# atmega_embedded_main_2.net
KiCad netlist of a schematic drawn in EAGLE
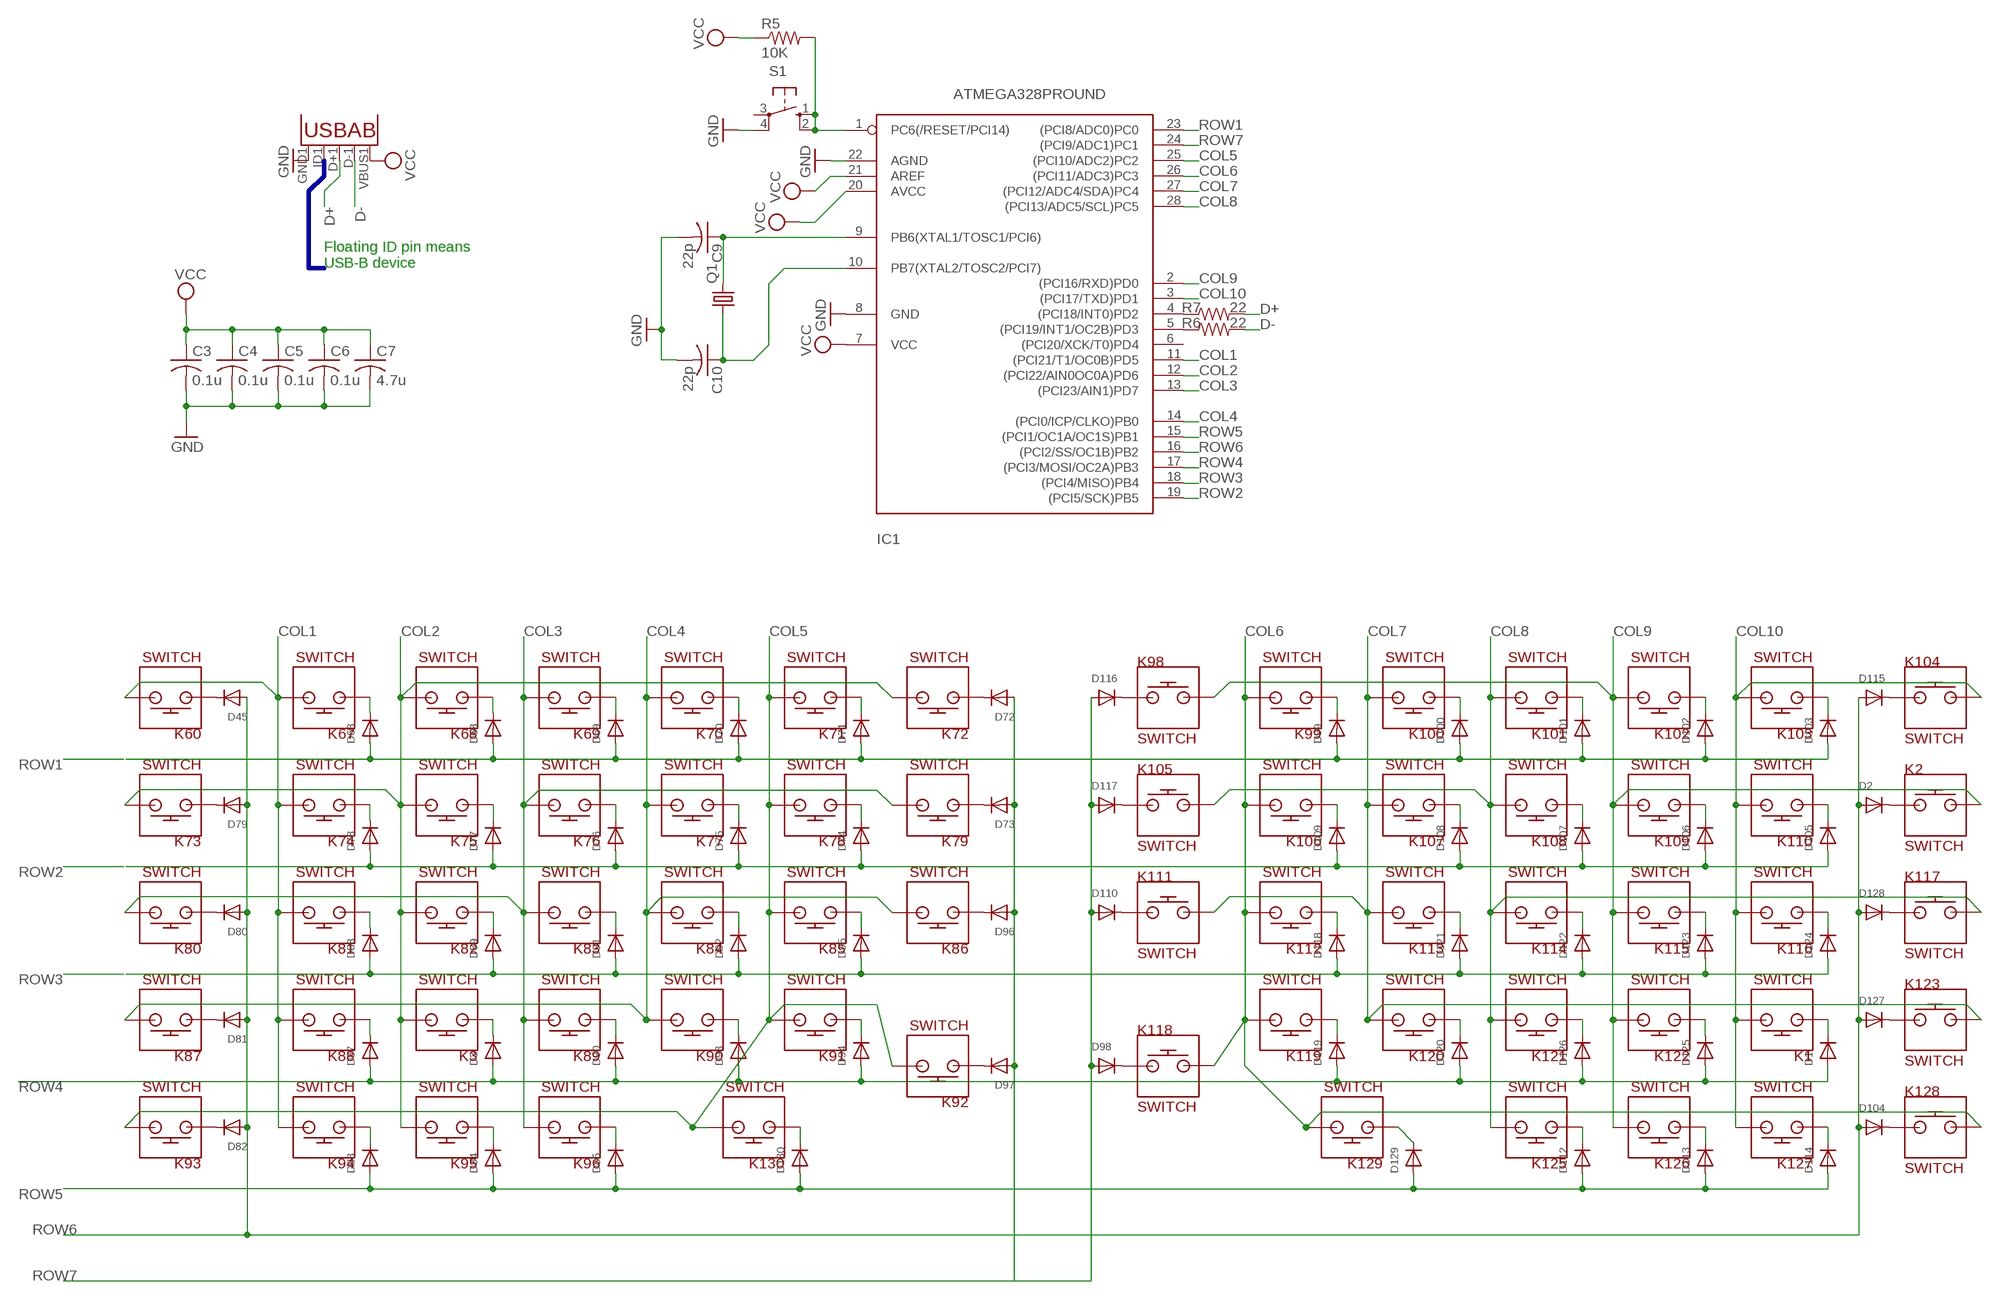
[diagram p0: schematic, sheet 1]

(export (version "E")
  (design (tool "Eeschema 10.0.6"))
  (components
    (comp (ref "C3")
      (value "0.1u")
      (footprint "eagle-import:C0805")
      (libsource (lib "eagle-import") (part "C-USC0805"))
    )
    (comp (ref "C4")
      (value "0.1u")
      (footprint "eagle-import:C0805")
      (libsource (lib "eagle-import") (part "C-USC0805"))
    )
    (comp (ref "C5")
      (value "0.1u")
      (footprint "eagle-import:C0805")
      (libsource (lib "eagle-import") (part "C-USC0805"))
    )
    (comp (ref "C6")
      (value "0.1u")
      (footprint "eagle-import:C0805")
      (libsource (lib "eagle-import") (part "C-USC0805"))
    )
    (comp (ref "C7")
      (value "4.7u")
      (footprint "eagle-import:C0805")
      (libsource (lib "eagle-import") (part "C-USC0805"))
    )
    (comp (ref "C9")
      (value "22p")
      (footprint "eagle-import:C0805")
      (libsource (lib "eagle-import") (part "C-USC0805"))
    )
    (comp (ref "C10")
      (value "22p")
      (footprint "eagle-import:C0805")
      (libsource (lib "eagle-import") (part "C-USC0805"))
    )
    (comp (ref "D1")
      (value "DIODESMA")
      (footprint "eagle-import:SMADIODE")
      (libsource (lib "eagle-import") (part "DIODESMA"))
    )
    (comp (ref "D2")
      (value "DIODESMA")
      (footprint "eagle-import:SMADIODE")
      (libsource (lib "eagle-import") (part "DIODESMA"))
    )
    (comp (ref "D3")
      (value "DIODESMA")
      (footprint "eagle-import:SMADIODE")
      (libsource (lib "eagle-import") (part "DIODESMA"))
    )
    (comp (ref "D45")
      (value "DIODESMA")
      (footprint "eagle-import:SMADIODE")
      (libsource (lib "eagle-import") (part "DIODESMA"))
    )
    (comp (ref "D63")
      (value "DIODESMA")
      (footprint "eagle-import:SMADIODE")
      (libsource (lib "eagle-import") (part "DIODESMA"))
    )
    (comp (ref "D68")
      (value "DIODESMA")
      (footprint "eagle-import:SMADIODE")
      (libsource (lib "eagle-import") (part "DIODESMA"))
    )
    (comp (ref "D69")
      (value "DIODESMA")
      (footprint "eagle-import:SMADIODE")
      (libsource (lib "eagle-import") (part "DIODESMA"))
    )
    (comp (ref "D70")
      (value "DIODESMA")
      (footprint "eagle-import:SMADIODE")
      (libsource (lib "eagle-import") (part "DIODESMA"))
    )
    (comp (ref "D71")
      (value "DIODESMA")
      (footprint "eagle-import:SMADIODE")
      (libsource (lib "eagle-import") (part "DIODESMA"))
    )
    (comp (ref "D72")
      (value "DIODESMA")
      (footprint "eagle-import:SMADIODE")
      (libsource (lib "eagle-import") (part "DIODESMA"))
    )
    (comp (ref "D73")
      (value "DIODESMA")
      (footprint "eagle-import:SMADIODE")
      (libsource (lib "eagle-import") (part "DIODESMA"))
    )
    (comp (ref "D74")
      (value "DIODESMA")
      (footprint "eagle-import:SMADIODE")
      (libsource (lib "eagle-import") (part "DIODESMA"))
    )
    (comp (ref "D75")
      (value "DIODESMA")
      (footprint "eagle-import:SMADIODE")
      (libsource (lib "eagle-import") (part "DIODESMA"))
    )
    (comp (ref "D76")
      (value "DIODESMA")
      (footprint "eagle-import:SMADIODE")
      (libsource (lib "eagle-import") (part "DIODESMA"))
    )
    (comp (ref "D77")
      (value "DIODESMA")
      (footprint "eagle-import:SMADIODE")
      (libsource (lib "eagle-import") (part "DIODESMA"))
    )
    (comp (ref "D78")
      (value "DIODESMA")
      (footprint "eagle-import:SMADIODE")
      (libsource (lib "eagle-import") (part "DIODESMA"))
    )
    (comp (ref "D79")
      (value "DIODESMA")
      (footprint "eagle-import:SMADIODE")
      (libsource (lib "eagle-import") (part "DIODESMA"))
    )
    (comp (ref "D80")
      (value "DIODESMA")
      (footprint "eagle-import:SMADIODE")
      (libsource (lib "eagle-import") (part "DIODESMA"))
    )
    (comp (ref "D81")
      (value "DIODESMA")
      (footprint "eagle-import:SMADIODE")
      (libsource (lib "eagle-import") (part "DIODESMA"))
    )
    (comp (ref "D82")
      (value "DIODESMA")
      (footprint "eagle-import:SMADIODE")
      (libsource (lib "eagle-import") (part "DIODESMA"))
    )
    (comp (ref "D83")
      (value "DIODESMA")
      (footprint "eagle-import:SMADIODE")
      (libsource (lib "eagle-import") (part "DIODESMA"))
    )
    (comp (ref "D84")
      (value "DIODESMA")
      (footprint "eagle-import:SMADIODE")
      (libsource (lib "eagle-import") (part "DIODESMA"))
    )
    (comp (ref "D85")
      (value "DIODESMA")
      (footprint "eagle-import:SMADIODE")
      (libsource (lib "eagle-import") (part "DIODESMA"))
    )
    (comp (ref "D87")
      (value "DIODESMA")
      (footprint "eagle-import:SMADIODE")
      (libsource (lib "eagle-import") (part "DIODESMA"))
    )
    (comp (ref "D88")
      (value "DIODESMA")
      (footprint "eagle-import:SMADIODE")
      (libsource (lib "eagle-import") (part "DIODESMA"))
    )
    (comp (ref "D89")
      (value "DIODESMA")
      (footprint "eagle-import:SMADIODE")
      (libsource (lib "eagle-import") (part "DIODESMA"))
    )
    (comp (ref "D90")
      (value "DIODESMA")
      (footprint "eagle-import:SMADIODE")
      (libsource (lib "eagle-import") (part "DIODESMA"))
    )
    (comp (ref "D91")
      (value "DIODESMA")
      (footprint "eagle-import:SMADIODE")
      (libsource (lib "eagle-import") (part "DIODESMA"))
    )
    (comp (ref "D92")
      (value "DIODESMA")
      (footprint "eagle-import:SMADIODE")
      (libsource (lib "eagle-import") (part "DIODESMA"))
    )
    (comp (ref "D93")
      (value "DIODESMA")
      (footprint "eagle-import:SMADIODE")
      (libsource (lib "eagle-import") (part "DIODESMA"))
    )
    (comp (ref "D94")
      (value "DIODESMA")
      (footprint "eagle-import:SMADIODE")
      (libsource (lib "eagle-import") (part "DIODESMA"))
    )
    (comp (ref "D95")
      (value "DIODESMA")
      (footprint "eagle-import:SMADIODE")
      (libsource (lib "eagle-import") (part "DIODESMA"))
    )
    (comp (ref "D96")
      (value "DIODESMA")
      (footprint "eagle-import:SMADIODE")
      (libsource (lib "eagle-import") (part "DIODESMA"))
    )
    (comp (ref "D97")
      (value "DIODESMA")
      (footprint "eagle-import:SMADIODE")
      (libsource (lib "eagle-import") (part "DIODESMA"))
    )
    (comp (ref "D98")
      (value "DIODESMA")
      (footprint "eagle-import:SMADIODE")
      (libsource (lib "eagle-import") (part "DIODESMA"))
    )
    (comp (ref "D99")
      (value "DIODESMA")
      (footprint "eagle-import:SMADIODE")
      (libsource (lib "eagle-import") (part "DIODESMA"))
    )
    (comp (ref "D100")
      (value "DIODESMA")
      (footprint "eagle-import:SMADIODE")
      (libsource (lib "eagle-import") (part "DIODESMA"))
    )
    (comp (ref "D101")
      (value "DIODESMA")
      (footprint "eagle-import:SMADIODE")
      (libsource (lib "eagle-import") (part "DIODESMA"))
    )
    (comp (ref "D102")
      (value "DIODESMA")
      (footprint "eagle-import:SMADIODE")
      (libsource (lib "eagle-import") (part "DIODESMA"))
    )
    (comp (ref "D103")
      (value "DIODESMA")
      (footprint "eagle-import:SMADIODE")
      (libsource (lib "eagle-import") (part "DIODESMA"))
    )
    (comp (ref "D104")
      (value "DIODESMA")
      (footprint "eagle-import:SMADIODE")
      (libsource (lib "eagle-import") (part "DIODESMA"))
    )
    (comp (ref "D105")
      (value "DIODESMA")
      (footprint "eagle-import:SMADIODE")
      (libsource (lib "eagle-import") (part "DIODESMA"))
    )
    (comp (ref "D106")
      (value "DIODESMA")
      (footprint "eagle-import:SMADIODE")
      (libsource (lib "eagle-import") (part "DIODESMA"))
    )
    (comp (ref "D107")
      (value "DIODESMA")
      (footprint "eagle-import:SMADIODE")
      (libsource (lib "eagle-import") (part "DIODESMA"))
    )
    (comp (ref "D108")
      (value "DIODESMA")
      (footprint "eagle-import:SMADIODE")
      (libsource (lib "eagle-import") (part "DIODESMA"))
    )
    (comp (ref "D109")
      (value "DIODESMA")
      (footprint "eagle-import:SMADIODE")
      (libsource (lib "eagle-import") (part "DIODESMA"))
    )
    (comp (ref "D110")
      (value "DIODESMA")
      (footprint "eagle-import:SMADIODE")
      (libsource (lib "eagle-import") (part "DIODESMA"))
    )
    (comp (ref "D112")
      (value "DIODESMA")
      (footprint "eagle-import:SMADIODE")
      (libsource (lib "eagle-import") (part "DIODESMA"))
    )
    (comp (ref "D113")
      (value "DIODESMA")
      (footprint "eagle-import:SMADIODE")
      (libsource (lib "eagle-import") (part "DIODESMA"))
    )
    (comp (ref "D114")
      (value "DIODESMA")
      (footprint "eagle-import:SMADIODE")
      (libsource (lib "eagle-import") (part "DIODESMA"))
    )
    (comp (ref "D115")
      (value "DIODESMA")
      (footprint "eagle-import:SMADIODE")
      (libsource (lib "eagle-import") (part "DIODESMA"))
    )
    (comp (ref "D116")
      (value "DIODESMA")
      (footprint "eagle-import:SMADIODE")
      (libsource (lib "eagle-import") (part "DIODESMA"))
    )
    (comp (ref "D117")
      (value "DIODESMA")
      (footprint "eagle-import:SMADIODE")
      (libsource (lib "eagle-import") (part "DIODESMA"))
    )
    (comp (ref "D118")
      (value "DIODESMA")
      (footprint "eagle-import:SMADIODE")
      (libsource (lib "eagle-import") (part "DIODESMA"))
    )
    (comp (ref "D119")
      (value "DIODESMA")
      (footprint "eagle-import:SMADIODE")
      (libsource (lib "eagle-import") (part "DIODESMA"))
    )
    (comp (ref "D120")
      (value "DIODESMA")
      (footprint "eagle-import:SMADIODE")
      (libsource (lib "eagle-import") (part "DIODESMA"))
    )
    (comp (ref "D121")
      (value "DIODESMA")
      (footprint "eagle-import:SMADIODE")
      (libsource (lib "eagle-import") (part "DIODESMA"))
    )
    (comp (ref "D122")
      (value "DIODESMA")
      (footprint "eagle-import:SMADIODE")
      (libsource (lib "eagle-import") (part "DIODESMA"))
    )
    (comp (ref "D123")
      (value "DIODESMA")
      (footprint "eagle-import:SMADIODE")
      (libsource (lib "eagle-import") (part "DIODESMA"))
    )
    (comp (ref "D124")
      (value "DIODESMA")
      (footprint "eagle-import:SMADIODE")
      (libsource (lib "eagle-import") (part "DIODESMA"))
    )
    (comp (ref "D125")
      (value "DIODESMA")
      (footprint "eagle-import:SMADIODE")
      (libsource (lib "eagle-import") (part "DIODESMA"))
    )
    (comp (ref "D126")
      (value "DIODESMA")
      (footprint "eagle-import:SMADIODE")
      (libsource (lib "eagle-import") (part "DIODESMA"))
    )
    (comp (ref "D127")
      (value "DIODESMA")
      (footprint "eagle-import:SMADIODE")
      (libsource (lib "eagle-import") (part "DIODESMA"))
    )
    (comp (ref "D128")
      (value "DIODESMA")
      (footprint "eagle-import:SMADIODE")
      (libsource (lib "eagle-import") (part "DIODESMA"))
    )
    (comp (ref "D129")
      (value "DIODESMA")
      (footprint "eagle-import:SMADIODE")
      (libsource (lib "eagle-import") (part "DIODESMA"))
    )
    (comp (ref "D130")
      (value "DIODESMA")
      (footprint "eagle-import:SMADIODE")
      (libsource (lib "eagle-import") (part "DIODESMA"))
    )
    (comp (ref "IC1")
      (value "ATMEGA328PROUND")
      (footprint "eagle-import:DIL28-3-ROUND")
      (libsource (lib "eagle-import") (part "ATMEGA328PROUND"))
    )
    (comp (ref "K1")
      (value "SWITCH")
      (footprint "eagle-import:KAILH_LOW_PROFILE")
      (libsource (lib "eagle-import") (part "SWITCH"))
    )
    (comp (ref "K2")
      (value "SWITCH")
      (footprint "eagle-import:KAILH_LOW_PROFILE")
      (libsource (lib "eagle-import") (part "SWITCH"))
    )
    (comp (ref "K3")
      (value "SWITCH")
      (footprint "eagle-import:KAILH_LOW_PROFILE")
      (libsource (lib "eagle-import") (part "SWITCH"))
    )
    (comp (ref "K60")
      (value "SWITCH")
      (footprint "eagle-import:KAILH_LOW_PROFILE")
      (libsource (lib "eagle-import") (part "SWITCH"))
    )
    (comp (ref "K67")
      (value "SWITCH")
      (footprint "eagle-import:KAILH_LOW_PROFILE")
      (libsource (lib "eagle-import") (part "SWITCH"))
    )
    (comp (ref "K68")
      (value "SWITCH")
      (footprint "eagle-import:KAILH_LOW_PROFILE")
      (libsource (lib "eagle-import") (part "SWITCH"))
    )
    (comp (ref "K69")
      (value "SWITCH")
      (footprint "eagle-import:KAILH_LOW_PROFILE")
      (libsource (lib "eagle-import") (part "SWITCH"))
    )
    (comp (ref "K70")
      (value "SWITCH")
      (footprint "eagle-import:KAILH_LOW_PROFILE")
      (libsource (lib "eagle-import") (part "SWITCH"))
    )
    (comp (ref "K71")
      (value "SWITCH")
      (footprint "eagle-import:KAILH_LOW_PROFILE")
      (libsource (lib "eagle-import") (part "SWITCH"))
    )
    (comp (ref "K72")
      (value "SWITCH")
      (footprint "eagle-import:KAILH_LOW_PROFILE")
      (libsource (lib "eagle-import") (part "SWITCH"))
    )
    (comp (ref "K73")
      (value "SWITCH")
      (footprint "eagle-import:KAILH_LOW_PROFILE")
      (libsource (lib "eagle-import") (part "SWITCH"))
    )
    (comp (ref "K74")
      (value "SWITCH")
      (footprint "eagle-import:KAILH_LOW_PROFILE")
      (libsource (lib "eagle-import") (part "SWITCH"))
    )
    (comp (ref "K75")
      (value "SWITCH")
      (footprint "eagle-import:KAILH_LOW_PROFILE")
      (libsource (lib "eagle-import") (part "SWITCH"))
    )
    (comp (ref "K76")
      (value "SWITCH")
      (footprint "eagle-import:KAILH_LOW_PROFILE")
      (libsource (lib "eagle-import") (part "SWITCH"))
    )
    (comp (ref "K77")
      (value "SWITCH")
      (footprint "eagle-import:KAILH_LOW_PROFILE")
      (libsource (lib "eagle-import") (part "SWITCH"))
    )
    (comp (ref "K78")
      (value "SWITCH")
      (footprint "eagle-import:KAILH_LOW_PROFILE")
      (libsource (lib "eagle-import") (part "SWITCH"))
    )
    (comp (ref "K79")
      (value "SWITCH")
      (footprint "eagle-import:KAILH_LOW_PROFILE")
      (libsource (lib "eagle-import") (part "SWITCH"))
    )
    (comp (ref "K80")
      (value "SWITCH")
      (footprint "eagle-import:KAILH_LOW_PROFILE")
      (libsource (lib "eagle-import") (part "SWITCH"))
    )
    (comp (ref "K81")
      (value "SWITCH")
      (footprint "eagle-import:KAILH_LOW_PROFILE")
      (libsource (lib "eagle-import") (part "SWITCH"))
    )
    (comp (ref "K82")
      (value "SWITCH")
      (footprint "eagle-import:KAILH_LOW_PROFILE")
      (libsource (lib "eagle-import") (part "SWITCH"))
    )
    (comp (ref "K83")
      (value "SWITCH")
      (footprint "eagle-import:KAILH_LOW_PROFILE")
      (libsource (lib "eagle-import") (part "SWITCH"))
    )
    (comp (ref "K84")
      (value "SWITCH")
      (footprint "eagle-import:KAILH_LOW_PROFILE")
      (libsource (lib "eagle-import") (part "SWITCH"))
    )
    (comp (ref "K85")
      (value "SWITCH")
      (footprint "eagle-import:KAILH_LOW_PROFILE")
      (libsource (lib "eagle-import") (part "SWITCH"))
    )
    (comp (ref "K86")
      (value "SWITCH")
      (footprint "eagle-import:KAILH_LOW_PROFILE")
      (libsource (lib "eagle-import") (part "SWITCH"))
    )
    (comp (ref "K87")
      (value "SWITCH")
      (footprint "eagle-import:KAILH_LOW_PROFILE")
      (libsource (lib "eagle-import") (part "SWITCH"))
    )
    (comp (ref "K88")
      (value "SWITCH")
      (footprint "eagle-import:KAILH_LOW_PROFILE")
      (libsource (lib "eagle-import") (part "SWITCH"))
    )
    (comp (ref "K89")
      (value "SWITCH")
      (footprint "eagle-import:KAILH_LOW_PROFILE")
      (libsource (lib "eagle-import") (part "SWITCH"))
    )
    (comp (ref "K90")
      (value "SWITCH")
      (footprint "eagle-import:KAILH_LOW_PROFILE")
      (libsource (lib "eagle-import") (part "SWITCH"))
    )
    (comp (ref "K91")
      (value "SWITCH")
      (footprint "eagle-import:KAILH_LOW_PROFILE")
      (libsource (lib "eagle-import") (part "SWITCH"))
    )
    (comp (ref "K92")
      (value "SWITCH")
      (footprint "eagle-import:KAILH_LOW_PROFILE")
      (libsource (lib "eagle-import") (part "SWITCH"))
    )
    (comp (ref "K93")
      (value "SWITCH")
      (footprint "eagle-import:KAILH_LOW_PROFILE")
      (libsource (lib "eagle-import") (part "SWITCH"))
    )
    (comp (ref "K94")
      (value "SWITCH")
      (footprint "eagle-import:KAILH_LOW_PROFILE")
      (libsource (lib "eagle-import") (part "SWITCH"))
    )
    (comp (ref "K95")
      (value "SWITCH")
      (footprint "eagle-import:KAILH_LOW_PROFILE")
      (libsource (lib "eagle-import") (part "SWITCH"))
    )
    (comp (ref "K96")
      (value "SWITCH")
      (footprint "eagle-import:KAILH_LOW_PROFILE")
      (libsource (lib "eagle-import") (part "SWITCH"))
    )
    (comp (ref "K98")
      (value "SWITCH")
      (footprint "eagle-import:KAILH_LOW_PROFILE")
      (libsource (lib "eagle-import") (part "SWITCH"))
    )
    (comp (ref "K99")
      (value "SWITCH")
      (footprint "eagle-import:KAILH_LOW_PROFILE")
      (libsource (lib "eagle-import") (part "SWITCH"))
    )
    (comp (ref "K100")
      (value "SWITCH")
      (footprint "eagle-import:KAILH_LOW_PROFILE")
      (libsource (lib "eagle-import") (part "SWITCH"))
    )
    (comp (ref "K101")
      (value "SWITCH")
      (footprint "eagle-import:KAILH_LOW_PROFILE")
      (libsource (lib "eagle-import") (part "SWITCH"))
    )
    (comp (ref "K102")
      (value "SWITCH")
      (footprint "eagle-import:KAILH_LOW_PROFILE")
      (libsource (lib "eagle-import") (part "SWITCH"))
    )
    (comp (ref "K103")
      (value "SWITCH")
      (footprint "eagle-import:KAILH_LOW_PROFILE")
      (libsource (lib "eagle-import") (part "SWITCH"))
    )
    (comp (ref "K104")
      (value "SWITCH")
      (footprint "eagle-import:KAILH_LOW_PROFILE")
      (libsource (lib "eagle-import") (part "SWITCH"))
    )
    (comp (ref "K105")
      (value "SWITCH")
      (footprint "eagle-import:KAILH_LOW_PROFILE")
      (libsource (lib "eagle-import") (part "SWITCH"))
    )
    (comp (ref "K106")
      (value "SWITCH")
      (footprint "eagle-import:KAILH_LOW_PROFILE")
      (libsource (lib "eagle-import") (part "SWITCH"))
    )
    (comp (ref "K107")
      (value "SWITCH")
      (footprint "eagle-import:KAILH_LOW_PROFILE")
      (libsource (lib "eagle-import") (part "SWITCH"))
    )
    (comp (ref "K108")
      (value "SWITCH")
      (footprint "eagle-import:KAILH_LOW_PROFILE")
      (libsource (lib "eagle-import") (part "SWITCH"))
    )
    (comp (ref "K109")
      (value "SWITCH")
      (footprint "eagle-import:KAILH_LOW_PROFILE")
      (libsource (lib "eagle-import") (part "SWITCH"))
    )
    (comp (ref "K110")
      (value "SWITCH")
      (footprint "eagle-import:KAILH_LOW_PROFILE")
      (libsource (lib "eagle-import") (part "SWITCH"))
    )
    (comp (ref "K111")
      (value "SWITCH")
      (footprint "eagle-import:KAILH_LOW_PROFILE")
      (libsource (lib "eagle-import") (part "SWITCH"))
    )
    (comp (ref "K112")
      (value "SWITCH")
      (footprint "eagle-import:KAILH_LOW_PROFILE")
      (libsource (lib "eagle-import") (part "SWITCH"))
    )
    (comp (ref "K113")
      (value "SWITCH")
      (footprint "eagle-import:KAILH_LOW_PROFILE")
      (libsource (lib "eagle-import") (part "SWITCH"))
    )
    (comp (ref "K114")
      (value "SWITCH")
      (footprint "eagle-import:KAILH_LOW_PROFILE")
      (libsource (lib "eagle-import") (part "SWITCH"))
    )
    (comp (ref "K115")
      (value "SWITCH")
      (footprint "eagle-import:KAILH_LOW_PROFILE")
      (libsource (lib "eagle-import") (part "SWITCH"))
    )
    (comp (ref "K116")
      (value "SWITCH")
      (footprint "eagle-import:KAILH_LOW_PROFILE")
      (libsource (lib "eagle-import") (part "SWITCH"))
    )
    (comp (ref "K117")
      (value "SWITCH")
      (footprint "eagle-import:KAILH_LOW_PROFILE")
      (libsource (lib "eagle-import") (part "SWITCH"))
    )
    (comp (ref "K118")
      (value "SWITCH")
      (footprint "eagle-import:KAILH_LOW_PROFILE")
      (libsource (lib "eagle-import") (part "SWITCH"))
    )
    (comp (ref "K119")
      (value "SWITCH")
      (footprint "eagle-import:KAILH_LOW_PROFILE")
      (libsource (lib "eagle-import") (part "SWITCH"))
    )
    (comp (ref "K120")
      (value "SWITCH")
      (footprint "eagle-import:KAILH_LOW_PROFILE")
      (libsource (lib "eagle-import") (part "SWITCH"))
    )
    (comp (ref "K121")
      (value "SWITCH")
      (footprint "eagle-import:KAILH_LOW_PROFILE")
      (libsource (lib "eagle-import") (part "SWITCH"))
    )
    (comp (ref "K122")
      (value "SWITCH")
      (footprint "eagle-import:KAILH_LOW_PROFILE")
      (libsource (lib "eagle-import") (part "SWITCH"))
    )
    (comp (ref "K123")
      (value "SWITCH")
      (footprint "eagle-import:KAILH_LOW_PROFILE")
      (libsource (lib "eagle-import") (part "SWITCH"))
    )
    (comp (ref "K125")
      (value "SWITCH")
      (footprint "eagle-import:KAILH_LOW_PROFILE")
      (libsource (lib "eagle-import") (part "SWITCH"))
    )
    (comp (ref "K126")
      (value "SWITCH")
      (footprint "eagle-import:KAILH_LOW_PROFILE")
      (libsource (lib "eagle-import") (part "SWITCH"))
    )
    (comp (ref "K127")
      (value "SWITCH")
      (footprint "eagle-import:KAILH_LOW_PROFILE")
      (libsource (lib "eagle-import") (part "SWITCH"))
    )
    (comp (ref "K128")
      (value "SWITCH")
      (footprint "eagle-import:KAILH_LOW_PROFILE")
      (libsource (lib "eagle-import") (part "SWITCH"))
    )
    (comp (ref "K129")
      (value "SWITCH")
      (footprint "eagle-import:KAILH_LOW_PROFILE")
      (libsource (lib "eagle-import") (part "SWITCH"))
    )
    (comp (ref "K130")
      (value "SWITCH")
      (footprint "eagle-import:KAILH_LOW_PROFILE")
      (libsource (lib "eagle-import") (part "SWITCH"))
    )
    (comp (ref "Q1")
      (value "CRYSTALHC49S")
      (footprint "eagle-import:HC49_S")
      (libsource (lib "eagle-import") (part "CRYSTALHC49S"))
    )
    (comp (ref "R5")
      (value "10K")
      (footprint "eagle-import:M0805")
      (libsource (lib "eagle-import") (part "R-US_M0805"))
    )
    (comp (ref "R6")
      (value "22")
      (footprint "eagle-import:M0805")
      (libsource (lib "eagle-import") (part "R-US_M0805"))
    )
    (comp (ref "R7")
      (value "22")
      (footprint "eagle-import:M0805")
      (libsource (lib "eagle-import") (part "R-US_M0805"))
    )
    (comp (ref "S1")
      (value "10-XX")
      (footprint "eagle-import:B3F-10XX")
      (fields (field (name "MPN") "B3F-1000"))
      (libsource (lib "eagle-import") (part "10-XX"))
    )
    (comp (ref "U1")
      (value "USB\"\"")
      (footprint "eagle-import:USB-MICRO-SMD")
      (libsource (lib "eagle-import") (part "USB{dblquote}{dblquote}"))
    )
  )
  (nets
    (net (code "1") (name "/COL1") (class "Default")
      (node (ref "IC1") (pin "11") (pinfunction "(PCI21/T1/OC0B)PD5_11") (pintype "bidirectional"))
      (node (ref "K60") (pin "P$2") (pinfunction "P$2_P$2") (pintype "bidirectional"))
      (node (ref "K67") (pin "P$2") (pinfunction "P$2_P$2") (pintype "bidirectional"))
      (node (ref "K74") (pin "P$2") (pinfunction "P$2_P$2") (pintype "bidirectional"))
      (node (ref "K81") (pin "P$2") (pinfunction "P$2_P$2") (pintype "bidirectional"))
      (node (ref "K88") (pin "P$2") (pinfunction "P$2_P$2") (pintype "bidirectional"))
      (node (ref "K94") (pin "P$2") (pinfunction "P$2_P$2") (pintype "bidirectional"))
    )
    (net (code "2") (name "/COL2") (class "Default")
      (node (ref "IC1") (pin "12") (pinfunction "(PCI22/AIN0OC0A)PD6_12") (pintype "bidirectional"))
      (node (ref "K3") (pin "P$2") (pinfunction "P$2_P$2") (pintype "bidirectional"))
      (node (ref "K68") (pin "P$2") (pinfunction "P$2_P$2") (pintype "bidirectional"))
      (node (ref "K72") (pin "P$2") (pinfunction "P$2_P$2") (pintype "bidirectional"))
      (node (ref "K73") (pin "P$2") (pinfunction "P$2_P$2") (pintype "bidirectional"))
      (node (ref "K75") (pin "P$2") (pinfunction "P$2_P$2") (pintype "bidirectional"))
      (node (ref "K82") (pin "P$2") (pinfunction "P$2_P$2") (pintype "bidirectional"))
      (node (ref "K95") (pin "P$2") (pinfunction "P$2_P$2") (pintype "bidirectional"))
    )
    (net (code "3") (name "/COL3") (class "Default")
      (node (ref "IC1") (pin "13") (pinfunction "(PCI23/AIN1)PD7_13") (pintype "bidirectional"))
      (node (ref "K69") (pin "P$2") (pinfunction "P$2_P$2") (pintype "bidirectional"))
      (node (ref "K76") (pin "P$2") (pinfunction "P$2_P$2") (pintype "bidirectional"))
      (node (ref "K79") (pin "P$2") (pinfunction "P$2_P$2") (pintype "bidirectional"))
      (node (ref "K80") (pin "P$2") (pinfunction "P$2_P$2") (pintype "bidirectional"))
      (node (ref "K83") (pin "P$2") (pinfunction "P$2_P$2") (pintype "bidirectional"))
      (node (ref "K89") (pin "P$2") (pinfunction "P$2_P$2") (pintype "bidirectional"))
      (node (ref "K96") (pin "P$2") (pinfunction "P$2_P$2") (pintype "bidirectional"))
    )
    (net (code "4") (name "/COL4") (class "Default")
      (node (ref "IC1") (pin "14") (pinfunction "(PCI0/ICP/CLKO)PB0_14") (pintype "bidirectional"))
      (node (ref "K70") (pin "P$2") (pinfunction "P$2_P$2") (pintype "bidirectional"))
      (node (ref "K77") (pin "P$2") (pinfunction "P$2_P$2") (pintype "bidirectional"))
      (node (ref "K84") (pin "P$2") (pinfunction "P$2_P$2") (pintype "bidirectional"))
      (node (ref "K86") (pin "P$2") (pinfunction "P$2_P$2") (pintype "bidirectional"))
      (node (ref "K87") (pin "P$2") (pinfunction "P$2_P$2") (pintype "bidirectional"))
      (node (ref "K90") (pin "P$2") (pinfunction "P$2_P$2") (pintype "bidirectional"))
    )
    (net (code "5") (name "/COL5") (class "Default")
      (node (ref "IC1") (pin "25") (pinfunction "(PCI10/ADC2)PC2_25") (pintype "bidirectional"))
      (node (ref "K130") (pin "P$2") (pinfunction "P$2_P$2") (pintype "bidirectional"))
      (node (ref "K71") (pin "P$2") (pinfunction "P$2_P$2") (pintype "bidirectional"))
      (node (ref "K78") (pin "P$2") (pinfunction "P$2_P$2") (pintype "bidirectional"))
      (node (ref "K85") (pin "P$2") (pinfunction "P$2_P$2") (pintype "bidirectional"))
      (node (ref "K91") (pin "P$2") (pinfunction "P$2_P$2") (pintype "bidirectional"))
      (node (ref "K92") (pin "P$2") (pinfunction "P$2_P$2") (pintype "bidirectional"))
      (node (ref "K93") (pin "P$2") (pinfunction "P$2_P$2") (pintype "bidirectional"))
    )
    (net (code "6") (name "/COL6") (class "Default")
      (node (ref "IC1") (pin "26") (pinfunction "(PCI11/ADC3)PC3_26") (pintype "bidirectional"))
      (node (ref "K106") (pin "P$2") (pinfunction "P$2_P$2") (pintype "bidirectional"))
      (node (ref "K112") (pin "P$2") (pinfunction "P$2_P$2") (pintype "bidirectional"))
      (node (ref "K118") (pin "P$2") (pinfunction "P$2_P$2") (pintype "bidirectional"))
      (node (ref "K119") (pin "P$2") (pinfunction "P$2_P$2") (pintype "bidirectional"))
      (node (ref "K128") (pin "P$2") (pinfunction "P$2_P$2") (pintype "bidirectional"))
      (node (ref "K129") (pin "P$2") (pinfunction "P$2_P$2") (pintype "bidirectional"))
      (node (ref "K99") (pin "P$2") (pinfunction "P$2_P$2") (pintype "bidirectional"))
    )
    (net (code "7") (name "/COL7") (class "Default")
      (node (ref "IC1") (pin "27") (pinfunction "(PCI12/ADC4/SDA)PC4_27") (pintype "bidirectional"))
      (node (ref "K100") (pin "P$2") (pinfunction "P$2_P$2") (pintype "bidirectional"))
      (node (ref "K107") (pin "P$2") (pinfunction "P$2_P$2") (pintype "bidirectional"))
      (node (ref "K111") (pin "P$2") (pinfunction "P$2_P$2") (pintype "bidirectional"))
      (node (ref "K113") (pin "P$2") (pinfunction "P$2_P$2") (pintype "bidirectional"))
      (node (ref "K120") (pin "P$2") (pinfunction "P$2_P$2") (pintype "bidirectional"))
      (node (ref "K123") (pin "P$2") (pinfunction "P$2_P$2") (pintype "bidirectional"))
    )
    (net (code "8") (name "/COL8") (class "Default")
      (node (ref "IC1") (pin "28") (pinfunction "(PCI13/ADC5/SCL)PC5_28") (pintype "bidirectional"))
      (node (ref "K101") (pin "P$2") (pinfunction "P$2_P$2") (pintype "bidirectional"))
      (node (ref "K105") (pin "P$2") (pinfunction "P$2_P$2") (pintype "bidirectional"))
      (node (ref "K108") (pin "P$2") (pinfunction "P$2_P$2") (pintype "bidirectional"))
      (node (ref "K114") (pin "P$2") (pinfunction "P$2_P$2") (pintype "bidirectional"))
      (node (ref "K117") (pin "P$2") (pinfunction "P$2_P$2") (pintype "bidirectional"))
      (node (ref "K121") (pin "P$2") (pinfunction "P$2_P$2") (pintype "bidirectional"))
      (node (ref "K125") (pin "P$2") (pinfunction "P$2_P$2") (pintype "bidirectional"))
    )
    (net (code "9") (name "/COL9") (class "Default")
      (node (ref "IC1") (pin "2") (pinfunction "(PCI16/RXD)PD0_2") (pintype "bidirectional"))
      (node (ref "K102") (pin "P$2") (pinfunction "P$2_P$2") (pintype "bidirectional"))
      (node (ref "K109") (pin "P$2") (pinfunction "P$2_P$2") (pintype "bidirectional"))
      (node (ref "K115") (pin "P$2") (pinfunction "P$2_P$2") (pintype "bidirectional"))
      (node (ref "K122") (pin "P$2") (pinfunction "P$2_P$2") (pintype "bidirectional"))
      (node (ref "K126") (pin "P$2") (pinfunction "P$2_P$2") (pintype "bidirectional"))
      (node (ref "K2") (pin "P$2") (pinfunction "P$2_P$2") (pintype "bidirectional"))
      (node (ref "K98") (pin "P$2") (pinfunction "P$2_P$2") (pintype "bidirectional"))
    )
    (net (code "10") (name "/COL10") (class "Default")
      (node (ref "IC1") (pin "3") (pinfunction "(PCI17/TXD)PD1_3") (pintype "bidirectional"))
      (node (ref "K1") (pin "P$2") (pinfunction "P$2_P$2") (pintype "bidirectional"))
      (node (ref "K103") (pin "P$2") (pinfunction "P$2_P$2") (pintype "bidirectional"))
      (node (ref "K104") (pin "P$2") (pinfunction "P$2_P$2") (pintype "bidirectional"))
      (node (ref "K110") (pin "P$2") (pinfunction "P$2_P$2") (pintype "bidirectional"))
      (node (ref "K116") (pin "P$2") (pinfunction "P$2_P$2") (pintype "bidirectional"))
      (node (ref "K127") (pin "P$2") (pinfunction "P$2_P$2") (pintype "bidirectional"))
    )
    (net (code "11") (name "/D+") (class "Default")
      (node (ref "R7") (pin "2") (pinfunction "2_2") (pintype "passive"))
      (node (ref "U1") (pin "D+1") (pinfunction "D+_D+1") (pintype "bidirectional"))
    )
    (net (code "12") (name "/D-") (class "Default")
      (node (ref "R6") (pin "2") (pinfunction "2_2") (pintype "passive"))
      (node (ref "U1") (pin "D-1") (pinfunction "D-_D-1") (pintype "bidirectional"))
    )
    (net (code "13") (name "/ROW1") (class "Default")
      (node (ref "D100") (pin "A") (pinfunction "A_A") (pintype "passive"))
      (node (ref "D101") (pin "A") (pinfunction "A_A") (pintype "passive"))
      (node (ref "D102") (pin "A") (pinfunction "A_A") (pintype "passive"))
      (node (ref "D103") (pin "A") (pinfunction "A_A") (pintype "passive"))
      (node (ref "D63") (pin "A") (pinfunction "A_A") (pintype "passive"))
      (node (ref "D68") (pin "A") (pinfunction "A_A") (pintype "passive"))
      (node (ref "D69") (pin "A") (pinfunction "A_A") (pintype "passive"))
      (node (ref "D70") (pin "A") (pinfunction "A_A") (pintype "passive"))
      (node (ref "D71") (pin "A") (pinfunction "A_A") (pintype "passive"))
      (node (ref "D99") (pin "A") (pinfunction "A_A") (pintype "passive"))
      (node (ref "IC1") (pin "23") (pinfunction "(PCI8/ADC0)PC0_23") (pintype "bidirectional"))
    )
    (net (code "14") (name "/ROW2") (class "Default")
      (node (ref "D105") (pin "A") (pinfunction "A_A") (pintype "passive"))
      (node (ref "D106") (pin "A") (pinfunction "A_A") (pintype "passive"))
      (node (ref "D107") (pin "A") (pinfunction "A_A") (pintype "passive"))
      (node (ref "D108") (pin "A") (pinfunction "A_A") (pintype "passive"))
      (node (ref "D109") (pin "A") (pinfunction "A_A") (pintype "passive"))
      (node (ref "D74") (pin "A") (pinfunction "A_A") (pintype "passive"))
      (node (ref "D75") (pin "A") (pinfunction "A_A") (pintype "passive"))
      (node (ref "D76") (pin "A") (pinfunction "A_A") (pintype "passive"))
      (node (ref "D77") (pin "A") (pinfunction "A_A") (pintype "passive"))
      (node (ref "D78") (pin "A") (pinfunction "A_A") (pintype "passive"))
      (node (ref "IC1") (pin "19") (pinfunction "(PCI5/SCK)PB5_19") (pintype "bidirectional"))
    )
    (net (code "15") (name "/ROW3") (class "Default")
      (node (ref "D118") (pin "A") (pinfunction "A_A") (pintype "passive"))
      (node (ref "D121") (pin "A") (pinfunction "A_A") (pintype "passive"))
      (node (ref "D122") (pin "A") (pinfunction "A_A") (pintype "passive"))
      (node (ref "D123") (pin "A") (pinfunction "A_A") (pintype "passive"))
      (node (ref "D124") (pin "A") (pinfunction "A_A") (pintype "passive"))
      (node (ref "D88") (pin "A") (pinfunction "A_A") (pintype "passive"))
      (node (ref "D89") (pin "A") (pinfunction "A_A") (pintype "passive"))
      (node (ref "D91") (pin "A") (pinfunction "A_A") (pintype "passive"))
      (node (ref "D92") (pin "A") (pinfunction "A_A") (pintype "passive"))
      (node (ref "D95") (pin "A") (pinfunction "A_A") (pintype "passive"))
      (node (ref "IC1") (pin "18") (pinfunction "(PCI4/MISO)PB4_18") (pintype "bidirectional"))
    )
    (net (code "16") (name "/ROW4") (class "Default")
      (node (ref "D1") (pin "A") (pinfunction "A_A") (pintype "passive"))
      (node (ref "D119") (pin "A") (pinfunction "A_A") (pintype "passive"))
      (node (ref "D120") (pin "A") (pinfunction "A_A") (pintype "passive"))
      (node (ref "D125") (pin "A") (pinfunction "A_A") (pintype "passive"))
      (node (ref "D126") (pin "A") (pinfunction "A_A") (pintype "passive"))
      (node (ref "D3") (pin "A") (pinfunction "A_A") (pintype "passive"))
      (node (ref "D87") (pin "A") (pinfunction "A_A") (pintype "passive"))
      (node (ref "D90") (pin "A") (pinfunction "A_A") (pintype "passive"))
      (node (ref "D93") (pin "A") (pinfunction "A_A") (pintype "passive"))
      (node (ref "D94") (pin "A") (pinfunction "A_A") (pintype "passive"))
      (node (ref "IC1") (pin "17") (pinfunction "(PCI3/MOSI/OC2A)PB3_17") (pintype "bidirectional"))
    )
    (net (code "17") (name "/ROW5") (class "Default")
      (node (ref "D112") (pin "A") (pinfunction "A_A") (pintype "passive"))
      (node (ref "D113") (pin "A") (pinfunction "A_A") (pintype "passive"))
      (node (ref "D114") (pin "A") (pinfunction "A_A") (pintype "passive"))
      (node (ref "D129") (pin "A") (pinfunction "A_A") (pintype "passive"))
      (node (ref "D130") (pin "A") (pinfunction "A_A") (pintype "passive"))
      (node (ref "D83") (pin "A") (pinfunction "A_A") (pintype "passive"))
      (node (ref "D84") (pin "A") (pinfunction "A_A") (pintype "passive"))
      (node (ref "D85") (pin "A") (pinfunction "A_A") (pintype "passive"))
      (node (ref "IC1") (pin "15") (pinfunction "(PCI1/OC1A/OC1S)PB1_15") (pintype "bidirectional"))
    )
    (net (code "18") (name "/ROW6") (class "Default")
      (node (ref "D104") (pin "A") (pinfunction "A_A") (pintype "passive"))
      (node (ref "D115") (pin "A") (pinfunction "A_A") (pintype "passive"))
      (node (ref "D127") (pin "A") (pinfunction "A_A") (pintype "passive"))
      (node (ref "D128") (pin "A") (pinfunction "A_A") (pintype "passive"))
      (node (ref "D2") (pin "A") (pinfunction "A_A") (pintype "passive"))
      (node (ref "D45") (pin "A") (pinfunction "A_A") (pintype "passive"))
      (node (ref "D79") (pin "A") (pinfunction "A_A") (pintype "passive"))
      (node (ref "D80") (pin "A") (pinfunction "A_A") (pintype "passive"))
      (node (ref "D81") (pin "A") (pinfunction "A_A") (pintype "passive"))
      (node (ref "D82") (pin "A") (pinfunction "A_A") (pintype "passive"))
      (node (ref "IC1") (pin "16") (pinfunction "(PCI2/SS/OC1B)PB2_16") (pintype "bidirectional"))
    )
    (net (code "19") (name "/ROW7") (class "Default")
      (node (ref "D110") (pin "A") (pinfunction "A_A") (pintype "passive"))
      (node (ref "D116") (pin "A") (pinfunction "A_A") (pintype "passive"))
      (node (ref "D117") (pin "A") (pinfunction "A_A") (pintype "passive"))
      (node (ref "D72") (pin "A") (pinfunction "A_A") (pintype "passive"))
      (node (ref "D73") (pin "A") (pinfunction "A_A") (pintype "passive"))
      (node (ref "D96") (pin "A") (pinfunction "A_A") (pintype "passive"))
      (node (ref "D97") (pin "A") (pinfunction "A_A") (pintype "passive"))
      (node (ref "D98") (pin "A") (pinfunction "A_A") (pintype "passive"))
      (node (ref "IC1") (pin "24") (pinfunction "(PCI9/ADC1)PC1_24") (pintype "bidirectional"))
    )
    (net (code "20") (name "GND") (class "Default")
      (node (ref "C10") (pin "2") (pinfunction "2_2") (pintype "passive"))
      (node (ref "C3") (pin "2") (pinfunction "2_2") (pintype "passive"))
      (node (ref "C4") (pin "2") (pinfunction "2_2") (pintype "passive"))
      (node (ref "C5") (pin "2") (pinfunction "2_2") (pintype "passive"))
      (node (ref "C6") (pin "2") (pinfunction "2_2") (pintype "passive"))
      (node (ref "C7") (pin "2") (pinfunction "2_2") (pintype "passive"))
      (node (ref "C9") (pin "2") (pinfunction "2_2") (pintype "passive"))
      (node (ref "IC1") (pin "22") (pinfunction "AGND_22") (pintype "bidirectional"))
      (node (ref "IC1") (pin "8") (pinfunction "GND_8") (pintype "bidirectional"))
      (node (ref "S1") (pin "4") (pinfunction "P1_4") (pintype "passive"))
      (node (ref "U1") (pin "GND1") (pinfunction "GND_GND1") (pintype "bidirectional"))
    )
    (net (code "21") (name "Net-(D1-PadC)") (class "Default")
      (node (ref "D1") (pin "C") (pinfunction "C_C") (pintype "passive"))
      (node (ref "K1") (pin "P$1") (pinfunction "P$1_P$1") (pintype "bidirectional"))
    )
    (net (code "22") (name "Net-(D2-PadC)") (class "Default")
      (node (ref "D2") (pin "C") (pinfunction "C_C") (pintype "passive"))
      (node (ref "K2") (pin "P$1") (pinfunction "P$1_P$1") (pintype "bidirectional"))
    )
    (net (code "23") (name "Net-(D3-PadC)") (class "Default")
      (node (ref "D3") (pin "C") (pinfunction "C_C") (pintype "passive"))
      (node (ref "K3") (pin "P$1") (pinfunction "P$1_P$1") (pintype "bidirectional"))
    )
    (net (code "24") (name "Net-(D45-PadC)") (class "Default")
      (node (ref "D45") (pin "C") (pinfunction "C_C") (pintype "passive"))
      (node (ref "K60") (pin "P$1") (pinfunction "P$1_P$1") (pintype "bidirectional"))
    )
    (net (code "25") (name "Net-(D63-PadC)") (class "Default")
      (node (ref "D63") (pin "C") (pinfunction "C_C") (pintype "passive"))
      (node (ref "K67") (pin "P$1") (pinfunction "P$1_P$1") (pintype "bidirectional"))
    )
    (net (code "26") (name "Net-(D68-PadC)") (class "Default")
      (node (ref "D68") (pin "C") (pinfunction "C_C") (pintype "passive"))
      (node (ref "K68") (pin "P$1") (pinfunction "P$1_P$1") (pintype "bidirectional"))
    )
    (net (code "27") (name "Net-(D69-PadC)") (class "Default")
      (node (ref "D69") (pin "C") (pinfunction "C_C") (pintype "passive"))
      (node (ref "K69") (pin "P$1") (pinfunction "P$1_P$1") (pintype "bidirectional"))
    )
    (net (code "28") (name "Net-(D70-PadC)") (class "Default")
      (node (ref "D70") (pin "C") (pinfunction "C_C") (pintype "passive"))
      (node (ref "K70") (pin "P$1") (pinfunction "P$1_P$1") (pintype "bidirectional"))
    )
    (net (code "29") (name "Net-(D71-PadC)") (class "Default")
      (node (ref "D71") (pin "C") (pinfunction "C_C") (pintype "passive"))
      (node (ref "K71") (pin "P$1") (pinfunction "P$1_P$1") (pintype "bidirectional"))
    )
    (net (code "30") (name "Net-(D72-PadC)") (class "Default")
      (node (ref "D72") (pin "C") (pinfunction "C_C") (pintype "passive"))
      (node (ref "K72") (pin "P$1") (pinfunction "P$1_P$1") (pintype "bidirectional"))
    )
    (net (code "31") (name "Net-(D73-PadC)") (class "Default")
      (node (ref "D73") (pin "C") (pinfunction "C_C") (pintype "passive"))
      (node (ref "K79") (pin "P$1") (pinfunction "P$1_P$1") (pintype "bidirectional"))
    )
    (net (code "32") (name "Net-(D74-PadC)") (class "Default")
      (node (ref "D74") (pin "C") (pinfunction "C_C") (pintype "passive"))
      (node (ref "K78") (pin "P$1") (pinfunction "P$1_P$1") (pintype "bidirectional"))
    )
    (net (code "33") (name "Net-(D75-PadC)") (class "Default")
      (node (ref "D75") (pin "C") (pinfunction "C_C") (pintype "passive"))
      (node (ref "K77") (pin "P$1") (pinfunction "P$1_P$1") (pintype "bidirectional"))
    )
    (net (code "34") (name "Net-(D76-PadC)") (class "Default")
      (node (ref "D76") (pin "C") (pinfunction "C_C") (pintype "passive"))
      (node (ref "K76") (pin "P$1") (pinfunction "P$1_P$1") (pintype "bidirectional"))
    )
    (net (code "35") (name "Net-(D77-PadC)") (class "Default")
      (node (ref "D77") (pin "C") (pinfunction "C_C") (pintype "passive"))
      (node (ref "K75") (pin "P$1") (pinfunction "P$1_P$1") (pintype "bidirectional"))
    )
    (net (code "36") (name "Net-(D78-PadC)") (class "Default")
      (node (ref "D78") (pin "C") (pinfunction "C_C") (pintype "passive"))
      (node (ref "K74") (pin "P$1") (pinfunction "P$1_P$1") (pintype "bidirectional"))
    )
    (net (code "37") (name "Net-(D79-PadC)") (class "Default")
      (node (ref "D79") (pin "C") (pinfunction "C_C") (pintype "passive"))
      (node (ref "K73") (pin "P$1") (pinfunction "P$1_P$1") (pintype "bidirectional"))
    )
    (net (code "38") (name "Net-(D80-PadC)") (class "Default")
      (node (ref "D80") (pin "C") (pinfunction "C_C") (pintype "passive"))
      (node (ref "K80") (pin "P$1") (pinfunction "P$1_P$1") (pintype "bidirectional"))
    )
    (net (code "39") (name "Net-(D81-PadC)") (class "Default")
      (node (ref "D81") (pin "C") (pinfunction "C_C") (pintype "passive"))
      (node (ref "K87") (pin "P$1") (pinfunction "P$1_P$1") (pintype "bidirectional"))
    )
    (net (code "40") (name "Net-(D82-PadC)") (class "Default")
      (node (ref "D82") (pin "C") (pinfunction "C_C") (pintype "passive"))
      (node (ref "K93") (pin "P$1") (pinfunction "P$1_P$1") (pintype "bidirectional"))
    )
    (net (code "41") (name "Net-(D83-PadC)") (class "Default")
      (node (ref "D83") (pin "C") (pinfunction "C_C") (pintype "passive"))
      (node (ref "K94") (pin "P$1") (pinfunction "P$1_P$1") (pintype "bidirectional"))
    )
    (net (code "42") (name "Net-(D84-PadC)") (class "Default")
      (node (ref "D84") (pin "C") (pinfunction "C_C") (pintype "passive"))
      (node (ref "K95") (pin "P$1") (pinfunction "P$1_P$1") (pintype "bidirectional"))
    )
    (net (code "43") (name "Net-(D85-PadC)") (class "Default")
      (node (ref "D85") (pin "C") (pinfunction "C_C") (pintype "passive"))
      (node (ref "K96") (pin "P$1") (pinfunction "P$1_P$1") (pintype "bidirectional"))
    )
    (net (code "44") (name "Net-(D87-PadC)") (class "Default")
      (node (ref "D87") (pin "C") (pinfunction "C_C") (pintype "passive"))
      (node (ref "K88") (pin "P$1") (pinfunction "P$1_P$1") (pintype "bidirectional"))
    )
    (net (code "45") (name "Net-(D88-PadC)") (class "Default")
      (node (ref "D88") (pin "C") (pinfunction "C_C") (pintype "passive"))
      (node (ref "K81") (pin "P$1") (pinfunction "P$1_P$1") (pintype "bidirectional"))
    )
    (net (code "46") (name "Net-(D89-PadC)") (class "Default")
      (node (ref "D89") (pin "C") (pinfunction "C_C") (pintype "passive"))
      (node (ref "K82") (pin "P$1") (pinfunction "P$1_P$1") (pintype "bidirectional"))
    )
    (net (code "47") (name "Net-(D90-PadC)") (class "Default")
      (node (ref "D90") (pin "C") (pinfunction "C_C") (pintype "passive"))
      (node (ref "K89") (pin "P$1") (pinfunction "P$1_P$1") (pintype "bidirectional"))
    )
    (net (code "48") (name "Net-(D91-PadC)") (class "Default")
      (node (ref "D91") (pin "C") (pinfunction "C_C") (pintype "passive"))
      (node (ref "K83") (pin "P$1") (pinfunction "P$1_P$1") (pintype "bidirectional"))
    )
    (net (code "49") (name "Net-(D92-PadC)") (class "Default")
      (node (ref "D92") (pin "C") (pinfunction "C_C") (pintype "passive"))
      (node (ref "K84") (pin "P$1") (pinfunction "P$1_P$1") (pintype "bidirectional"))
    )
    (net (code "50") (name "Net-(D93-PadC)") (class "Default")
      (node (ref "D93") (pin "C") (pinfunction "C_C") (pintype "passive"))
      (node (ref "K90") (pin "P$1") (pinfunction "P$1_P$1") (pintype "bidirectional"))
    )
    (net (code "51") (name "Net-(D94-PadC)") (class "Default")
      (node (ref "D94") (pin "C") (pinfunction "C_C") (pintype "passive"))
      (node (ref "K91") (pin "P$1") (pinfunction "P$1_P$1") (pintype "bidirectional"))
    )
    (net (code "52") (name "Net-(D95-PadC)") (class "Default")
      (node (ref "D95") (pin "C") (pinfunction "C_C") (pintype "passive"))
      (node (ref "K85") (pin "P$1") (pinfunction "P$1_P$1") (pintype "bidirectional"))
    )
    (net (code "53") (name "Net-(D96-PadC)") (class "Default")
      (node (ref "D96") (pin "C") (pinfunction "C_C") (pintype "passive"))
      (node (ref "K86") (pin "P$1") (pinfunction "P$1_P$1") (pintype "bidirectional"))
    )
    (net (code "54") (name "Net-(D97-PadC)") (class "Default")
      (node (ref "D97") (pin "C") (pinfunction "C_C") (pintype "passive"))
      (node (ref "K92") (pin "P$1") (pinfunction "P$1_P$1") (pintype "bidirectional"))
    )
    (net (code "55") (name "Net-(D98-PadC)") (class "Default")
      (node (ref "D98") (pin "C") (pinfunction "C_C") (pintype "passive"))
      (node (ref "K118") (pin "P$1") (pinfunction "P$1_P$1") (pintype "bidirectional"))
    )
    (net (code "56") (name "Net-(D99-PadC)") (class "Default")
      (node (ref "D99") (pin "C") (pinfunction "C_C") (pintype "passive"))
      (node (ref "K99") (pin "P$1") (pinfunction "P$1_P$1") (pintype "bidirectional"))
    )
    (net (code "57") (name "Net-(D100-PadC)") (class "Default")
      (node (ref "D100") (pin "C") (pinfunction "C_C") (pintype "passive"))
      (node (ref "K100") (pin "P$1") (pinfunction "P$1_P$1") (pintype "bidirectional"))
    )
    (net (code "58") (name "Net-(D101-PadC)") (class "Default")
      (node (ref "D101") (pin "C") (pinfunction "C_C") (pintype "passive"))
      (node (ref "K101") (pin "P$1") (pinfunction "P$1_P$1") (pintype "bidirectional"))
    )
    (net (code "59") (name "Net-(D102-PadC)") (class "Default")
      (node (ref "D102") (pin "C") (pinfunction "C_C") (pintype "passive"))
      (node (ref "K102") (pin "P$1") (pinfunction "P$1_P$1") (pintype "bidirectional"))
    )
    (net (code "60") (name "Net-(D103-PadC)") (class "Default")
      (node (ref "D103") (pin "C") (pinfunction "C_C") (pintype "passive"))
      (node (ref "K103") (pin "P$1") (pinfunction "P$1_P$1") (pintype "bidirectional"))
    )
    (net (code "61") (name "Net-(D104-PadC)") (class "Default")
      (node (ref "D104") (pin "C") (pinfunction "C_C") (pintype "passive"))
      (node (ref "K128") (pin "P$1") (pinfunction "P$1_P$1") (pintype "bidirectional"))
    )
    (net (code "62") (name "Net-(D105-PadC)") (class "Default")
      (node (ref "D105") (pin "C") (pinfunction "C_C") (pintype "passive"))
      (node (ref "K110") (pin "P$1") (pinfunction "P$1_P$1") (pintype "bidirectional"))
    )
    (net (code "63") (name "Net-(D106-PadC)") (class "Default")
      (node (ref "D106") (pin "C") (pinfunction "C_C") (pintype "passive"))
      (node (ref "K109") (pin "P$1") (pinfunction "P$1_P$1") (pintype "bidirectional"))
    )
    (net (code "64") (name "Net-(D107-PadC)") (class "Default")
      (node (ref "D107") (pin "C") (pinfunction "C_C") (pintype "passive"))
      (node (ref "K108") (pin "P$1") (pinfunction "P$1_P$1") (pintype "bidirectional"))
    )
    (net (code "65") (name "Net-(D108-PadC)") (class "Default")
      (node (ref "D108") (pin "C") (pinfunction "C_C") (pintype "passive"))
      (node (ref "K107") (pin "P$1") (pinfunction "P$1_P$1") (pintype "bidirectional"))
    )
    (net (code "66") (name "Net-(D109-PadC)") (class "Default")
      (node (ref "D109") (pin "C") (pinfunction "C_C") (pintype "passive"))
      (node (ref "K106") (pin "P$1") (pinfunction "P$1_P$1") (pintype "bidirectional"))
    )
    (net (code "67") (name "Net-(D110-PadC)") (class "Default")
      (node (ref "D110") (pin "C") (pinfunction "C_C") (pintype "passive"))
      (node (ref "K111") (pin "P$1") (pinfunction "P$1_P$1") (pintype "bidirectional"))
    )
    (net (code "68") (name "Net-(D112-PadC)") (class "Default")
      (node (ref "D112") (pin "C") (pinfunction "C_C") (pintype "passive"))
      (node (ref "K125") (pin "P$1") (pinfunction "P$1_P$1") (pintype "bidirectional"))
    )
    (net (code "69") (name "Net-(D113-PadC)") (class "Default")
      (node (ref "D113") (pin "C") (pinfunction "C_C") (pintype "passive"))
      (node (ref "K126") (pin "P$1") (pinfunction "P$1_P$1") (pintype "bidirectional"))
    )
    (net (code "70") (name "Net-(D114-PadC)") (class "Default")
      (node (ref "D114") (pin "C") (pinfunction "C_C") (pintype "passive"))
      (node (ref "K127") (pin "P$1") (pinfunction "P$1_P$1") (pintype "bidirectional"))
    )
    (net (code "71") (name "Net-(D115-PadC)") (class "Default")
      (node (ref "D115") (pin "C") (pinfunction "C_C") (pintype "passive"))
      (node (ref "K104") (pin "P$1") (pinfunction "P$1_P$1") (pintype "bidirectional"))
    )
    (net (code "72") (name "Net-(D116-PadC)") (class "Default")
      (node (ref "D116") (pin "C") (pinfunction "C_C") (pintype "passive"))
      (node (ref "K98") (pin "P$1") (pinfunction "P$1_P$1") (pintype "bidirectional"))
    )
    (net (code "73") (name "Net-(D117-PadC)") (class "Default")
      (node (ref "D117") (pin "C") (pinfunction "C_C") (pintype "passive"))
      (node (ref "K105") (pin "P$1") (pinfunction "P$1_P$1") (pintype "bidirectional"))
    )
    (net (code "74") (name "Net-(D118-PadC)") (class "Default")
      (node (ref "D118") (pin "C") (pinfunction "C_C") (pintype "passive"))
      (node (ref "K112") (pin "P$1") (pinfunction "P$1_P$1") (pintype "bidirectional"))
    )
    (net (code "75") (name "Net-(D119-PadC)") (class "Default")
      (node (ref "D119") (pin "C") (pinfunction "C_C") (pintype "passive"))
      (node (ref "K119") (pin "P$1") (pinfunction "P$1_P$1") (pintype "bidirectional"))
    )
    (net (code "76") (name "Net-(D120-PadC)") (class "Default")
      (node (ref "D120") (pin "C") (pinfunction "C_C") (pintype "passive"))
      (node (ref "K120") (pin "P$1") (pinfunction "P$1_P$1") (pintype "bidirectional"))
    )
    (net (code "77") (name "Net-(D121-PadC)") (class "Default")
      (node (ref "D121") (pin "C") (pinfunction "C_C") (pintype "passive"))
      (node (ref "K113") (pin "P$1") (pinfunction "P$1_P$1") (pintype "bidirectional"))
    )
    (net (code "78") (name "Net-(D122-PadC)") (class "Default")
      (node (ref "D122") (pin "C") (pinfunction "C_C") (pintype "passive"))
      (node (ref "K114") (pin "P$1") (pinfunction "P$1_P$1") (pintype "bidirectional"))
    )
    (net (code "79") (name "Net-(D123-PadC)") (class "Default")
      (node (ref "D123") (pin "C") (pinfunction "C_C") (pintype "passive"))
      (node (ref "K115") (pin "P$1") (pinfunction "P$1_P$1") (pintype "bidirectional"))
    )
    (net (code "80") (name "Net-(D124-PadC)") (class "Default")
      (node (ref "D124") (pin "C") (pinfunction "C_C") (pintype "passive"))
      (node (ref "K116") (pin "P$1") (pinfunction "P$1_P$1") (pintype "bidirectional"))
    )
    (net (code "81") (name "Net-(D125-PadC)") (class "Default")
      (node (ref "D125") (pin "C") (pinfunction "C_C") (pintype "passive"))
      (node (ref "K122") (pin "P$1") (pinfunction "P$1_P$1") (pintype "bidirectional"))
    )
    (net (code "82") (name "Net-(D126-PadC)") (class "Default")
      (node (ref "D126") (pin "C") (pinfunction "C_C") (pintype "passive"))
      (node (ref "K121") (pin "P$1") (pinfunction "P$1_P$1") (pintype "bidirectional"))
    )
    (net (code "83") (name "Net-(D127-PadC)") (class "Default")
      (node (ref "D127") (pin "C") (pinfunction "C_C") (pintype "passive"))
      (node (ref "K123") (pin "P$1") (pinfunction "P$1_P$1") (pintype "bidirectional"))
    )
    (net (code "84") (name "Net-(D128-PadC)") (class "Default")
      (node (ref "D128") (pin "C") (pinfunction "C_C") (pintype "passive"))
      (node (ref "K117") (pin "P$1") (pinfunction "P$1_P$1") (pintype "bidirectional"))
    )
    (net (code "85") (name "Net-(D129-PadC)") (class "Default")
      (node (ref "D129") (pin "C") (pinfunction "C_C") (pintype "passive"))
      (node (ref "K129") (pin "P$1") (pinfunction "P$1_P$1") (pintype "bidirectional"))
    )
    (net (code "86") (name "Net-(D130-PadC)") (class "Default")
      (node (ref "D130") (pin "C") (pinfunction "C_C") (pintype "passive"))
      (node (ref "K130") (pin "P$1") (pinfunction "P$1_P$1") (pintype "bidirectional"))
    )
    (net (code "87") (name "Net-(IC1-(PCI18{slash}INT0)PD2)") (class "Default")
      (node (ref "IC1") (pin "4") (pinfunction "(PCI18/INT0)PD2_4") (pintype "bidirectional"))
      (node (ref "R7") (pin "1") (pinfunction "1_1") (pintype "passive"))
    )
    (net (code "88") (name "Net-(IC1-(PCI19{slash}INT1{slash}OC2B)PD3)") (class "Default")
      (node (ref "IC1") (pin "5") (pinfunction "(PCI19/INT1/OC2B)PD3_5") (pintype "bidirectional"))
      (node (ref "R6") (pin "1") (pinfunction "1_1") (pintype "passive"))
    )
    (net (code "89") (name "Net-(IC1-PB6(XTAL1{slash}TOSC1{slash}PCI6))") (class "Default")
      (node (ref "C9") (pin "1") (pinfunction "1_1") (pintype "passive"))
      (node (ref "IC1") (pin "9") (pinfunction "PB6(XTAL1/TOSC1/PCI6)_9") (pintype "bidirectional"))
      (node (ref "Q1") (pin "2") (pinfunction "2_2") (pintype "passive"))
    )
    (net (code "90") (name "Net-(IC1-PB7(XTAL2{slash}TOSC2{slash}PCI7))") (class "Default")
      (node (ref "C10") (pin "1") (pinfunction "1_1") (pintype "passive"))
      (node (ref "IC1") (pin "10") (pinfunction "PB7(XTAL2/TOSC2/PCI7)_10") (pintype "bidirectional"))
      (node (ref "Q1") (pin "1") (pinfunction "1_1") (pintype "passive"))
    )
    (net (code "91") (name "Net-(IC1-PC6({slash}RESET{slash}PCI14))") (class "Default")
      (node (ref "IC1") (pin "1") (pinfunction "PC6(/RESET/PCI14)_1") (pintype "bidirectional"))
      (node (ref "R5") (pin "2") (pinfunction "2_2") (pintype "passive"))
      (node (ref "S1") (pin "1") (pinfunction "S_1") (pintype "passive"))
      (node (ref "S1") (pin "2") (pinfunction "S1_2") (pintype "passive"))
    )
    (net (code "92") (name "VCC") (class "Default")
      (node (ref "C3") (pin "1") (pinfunction "1_1") (pintype "passive"))
      (node (ref "C4") (pin "1") (pinfunction "1_1") (pintype "passive"))
      (node (ref "C5") (pin "1") (pinfunction "1_1") (pintype "passive"))
      (node (ref "C6") (pin "1") (pinfunction "1_1") (pintype "passive"))
      (node (ref "C7") (pin "1") (pinfunction "1_1") (pintype "passive"))
      (node (ref "IC1") (pin "20") (pinfunction "AVCC_20") (pintype "bidirectional"))
      (node (ref "IC1") (pin "21") (pinfunction "AREF_21") (pintype "bidirectional"))
      (node (ref "IC1") (pin "7") (pinfunction "VCC_7") (pintype "bidirectional"))
      (node (ref "R5") (pin "1") (pinfunction "1_1") (pintype "passive"))
      (node (ref "U1") (pin "VBUS1") (pinfunction "VBUS_VBUS1") (pintype "bidirectional"))
    )
    (net (code "93") (name "unconnected-(IC1-(PCI20{slash}XCK{slash}T0)PD4-Pad6)") (class "Default")
      (node (ref "IC1") (pin "6") (pinfunction "(PCI20/XCK/T0)PD4_6") (pintype "bidirectional"))
    )
    (net (code "94") (name "unconnected-(S1-P-Pad3)") (class "Default")
      (node (ref "S1") (pin "3") (pinfunction "P_3") (pintype "passive"))
    )
    (net (code "95") (name "unconnected-(U1-USBID-PadID1)") (class "Default")
      (node (ref "U1") (pin "ID1") (pinfunction "USBID_ID1") (pintype "bidirectional"))
    )
  )
)
